# mSD-Shield-Mega_v12.net
KiCad netlist of a schematic drawn in EAGLE
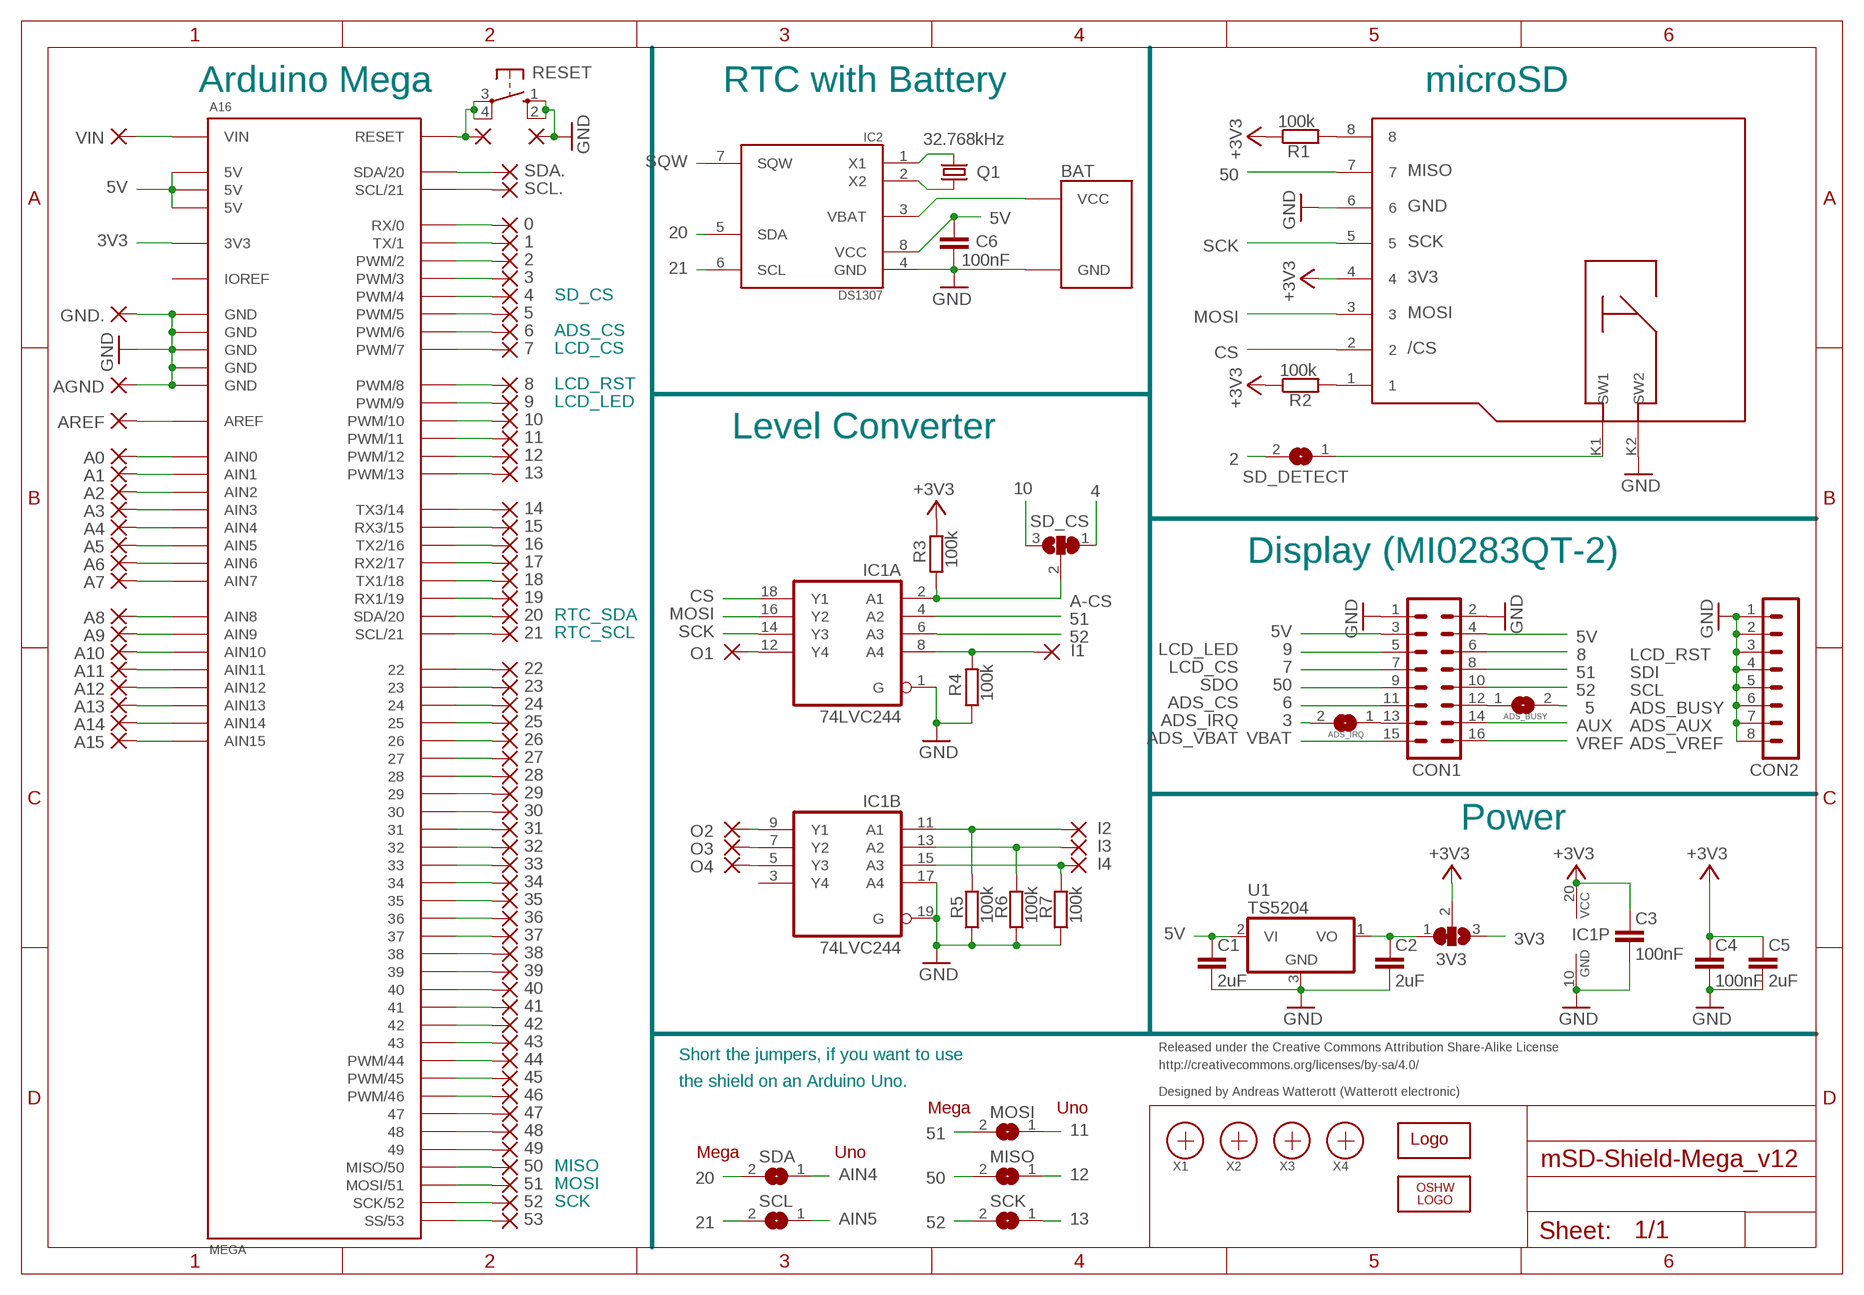
[diagram p0: schematic, sheet 1]

(export (version "E")
  (design (tool "Eeschema 10.0.6"))
  (components
    (comp (ref "0")
      (value "1,6/0,8")
      (footprint "eagle-import:1,6_0,8")
      (libsource (lib "eagle-import") (part "1,6/0,8"))
    )
    (comp (ref "1")
      (value "1,6/0,8")
      (footprint "eagle-import:1,6_0,8")
      (libsource (lib "eagle-import") (part "1,6/0,8"))
    )
    (comp (ref "2")
      (value "1,6/0,8")
      (footprint "eagle-import:1,6_0,8")
      (libsource (lib "eagle-import") (part "1,6/0,8"))
    )
    (comp (ref "3")
      (value "1,6/0,8")
      (footprint "eagle-import:1,6_0,8")
      (libsource (lib "eagle-import") (part "1,6/0,8"))
    )
    (comp (ref "3V3")
      (value "SJ2W")
      (footprint "eagle-import:SJ_2")
      (libsource (lib "eagle-import") (part "SJ2W"))
    )
    (comp (ref "4")
      (value "1,6/0,8")
      (footprint "eagle-import:1,6_0,8")
      (libsource (lib "eagle-import") (part "1,6/0,8"))
    )
    (comp (ref "5")
      (value "1,6/0,8")
      (footprint "eagle-import:1,6_0,8")
      (libsource (lib "eagle-import") (part "1,6/0,8"))
    )
    (comp (ref "6")
      (value "1,6/0,8")
      (footprint "eagle-import:1,6_0,8")
      (libsource (lib "eagle-import") (part "1,6/0,8"))
    )
    (comp (ref "7")
      (value "1,6/0,8")
      (footprint "eagle-import:1,6_0,8")
      (libsource (lib "eagle-import") (part "1,6/0,8"))
    )
    (comp (ref "8")
      (value "1,6/0,8")
      (footprint "eagle-import:1,6_0,8")
      (libsource (lib "eagle-import") (part "1,6/0,8"))
    )
    (comp (ref "9")
      (value "1,6/0,8")
      (footprint "eagle-import:1,6_0,8")
      (libsource (lib "eagle-import") (part "1,6/0,8"))
    )
    (comp (ref "10")
      (value "1,6/0,8")
      (footprint "eagle-import:1,6_0,8")
      (libsource (lib "eagle-import") (part "1,6/0,8"))
    )
    (comp (ref "11")
      (value "1,6/0,8")
      (footprint "eagle-import:1,6_0,8")
      (libsource (lib "eagle-import") (part "1,6/0,8"))
    )
    (comp (ref "12")
      (value "1,6/0,8")
      (footprint "eagle-import:1,6_0,8")
      (libsource (lib "eagle-import") (part "1,6/0,8"))
    )
    (comp (ref "13")
      (value "1,6/0,8")
      (footprint "eagle-import:1,6_0,8")
      (libsource (lib "eagle-import") (part "1,6/0,8"))
    )
    (comp (ref "14")
      (value "1,6/0,8")
      (footprint "eagle-import:1,6_0,8")
      (libsource (lib "eagle-import") (part "1,6/0,8"))
    )
    (comp (ref "15")
      (value "1,6/0,8")
      (footprint "eagle-import:1,6_0,8")
      (libsource (lib "eagle-import") (part "1,6/0,8"))
    )
    (comp (ref "16")
      (value "1,6/0,8")
      (footprint "eagle-import:1,6_0,8")
      (libsource (lib "eagle-import") (part "1,6/0,8"))
    )
    (comp (ref "17")
      (value "1,6/0,8")
      (footprint "eagle-import:1,6_0,8")
      (libsource (lib "eagle-import") (part "1,6/0,8"))
    )
    (comp (ref "18")
      (value "1,6/0,8")
      (footprint "eagle-import:1,6_0,8")
      (libsource (lib "eagle-import") (part "1,6/0,8"))
    )
    (comp (ref "19")
      (value "1,6/0,8")
      (footprint "eagle-import:1,6_0,8")
      (libsource (lib "eagle-import") (part "1,6/0,8"))
    )
    (comp (ref "20")
      (value "1,6/0,8")
      (footprint "eagle-import:1,6_0,8")
      (libsource (lib "eagle-import") (part "1,6/0,8"))
    )
    (comp (ref "21")
      (value "1,6/0,8")
      (footprint "eagle-import:1,6_0,8")
      (libsource (lib "eagle-import") (part "1,6/0,8"))
    )
    (comp (ref "22")
      (value "1,6/0,8")
      (footprint "eagle-import:1,6_0,8")
      (libsource (lib "eagle-import") (part "1,6/0,8"))
    )
    (comp (ref "23")
      (value "1,6/0,8")
      (footprint "eagle-import:1,6_0,8")
      (libsource (lib "eagle-import") (part "1,6/0,8"))
    )
    (comp (ref "24")
      (value "1,6/0,8")
      (footprint "eagle-import:1,6_0,8")
      (libsource (lib "eagle-import") (part "1,6/0,8"))
    )
    (comp (ref "25")
      (value "1,6/0,8")
      (footprint "eagle-import:1,6_0,8")
      (libsource (lib "eagle-import") (part "1,6/0,8"))
    )
    (comp (ref "26")
      (value "1,6/0,8")
      (footprint "eagle-import:1,6_0,8")
      (libsource (lib "eagle-import") (part "1,6/0,8"))
    )
    (comp (ref "27")
      (value "1,6/0,8")
      (footprint "eagle-import:1,6_0,8")
      (libsource (lib "eagle-import") (part "1,6/0,8"))
    )
    (comp (ref "28")
      (value "1,6/0,8")
      (footprint "eagle-import:1,6_0,8")
      (libsource (lib "eagle-import") (part "1,6/0,8"))
    )
    (comp (ref "29")
      (value "1,6/0,8")
      (footprint "eagle-import:1,6_0,8")
      (libsource (lib "eagle-import") (part "1,6/0,8"))
    )
    (comp (ref "30")
      (value "1,6/0,8")
      (footprint "eagle-import:1,6_0,8")
      (libsource (lib "eagle-import") (part "1,6/0,8"))
    )
    (comp (ref "31")
      (value "1,6/0,8")
      (footprint "eagle-import:1,6_0,8")
      (libsource (lib "eagle-import") (part "1,6/0,8"))
    )
    (comp (ref "32")
      (value "1,6/0,8")
      (footprint "eagle-import:1,6_0,8")
      (libsource (lib "eagle-import") (part "1,6/0,8"))
    )
    (comp (ref "33")
      (value "1,6/0,8")
      (footprint "eagle-import:1,6_0,8")
      (libsource (lib "eagle-import") (part "1,6/0,8"))
    )
    (comp (ref "34")
      (value "1,6/0,8")
      (footprint "eagle-import:1,6_0,8")
      (libsource (lib "eagle-import") (part "1,6/0,8"))
    )
    (comp (ref "35")
      (value "1,6/0,8")
      (footprint "eagle-import:1,6_0,8")
      (libsource (lib "eagle-import") (part "1,6/0,8"))
    )
    (comp (ref "36")
      (value "1,6/0,8")
      (footprint "eagle-import:1,6_0,8")
      (libsource (lib "eagle-import") (part "1,6/0,8"))
    )
    (comp (ref "37")
      (value "1,6/0,8")
      (footprint "eagle-import:1,6_0,8")
      (libsource (lib "eagle-import") (part "1,6/0,8"))
    )
    (comp (ref "38")
      (value "1,6/0,8")
      (footprint "eagle-import:1,6_0,8")
      (libsource (lib "eagle-import") (part "1,6/0,8"))
    )
    (comp (ref "39")
      (value "1,6/0,8")
      (footprint "eagle-import:1,6_0,8")
      (libsource (lib "eagle-import") (part "1,6/0,8"))
    )
    (comp (ref "40")
      (value "1,6/0,8")
      (footprint "eagle-import:1,6_0,8")
      (libsource (lib "eagle-import") (part "1,6/0,8"))
    )
    (comp (ref "41")
      (value "1,6/0,8")
      (footprint "eagle-import:1,6_0,8")
      (libsource (lib "eagle-import") (part "1,6/0,8"))
    )
    (comp (ref "42")
      (value "1,6/0,8")
      (footprint "eagle-import:1,6_0,8")
      (libsource (lib "eagle-import") (part "1,6/0,8"))
    )
    (comp (ref "43")
      (value "1,6/0,8")
      (footprint "eagle-import:1,6_0,8")
      (libsource (lib "eagle-import") (part "1,6/0,8"))
    )
    (comp (ref "44")
      (value "1,6/0,8")
      (footprint "eagle-import:1,6_0,8")
      (libsource (lib "eagle-import") (part "1,6/0,8"))
    )
    (comp (ref "45")
      (value "1,6/0,8")
      (footprint "eagle-import:1,6_0,8")
      (libsource (lib "eagle-import") (part "1,6/0,8"))
    )
    (comp (ref "46")
      (value "1,6/0,8")
      (footprint "eagle-import:1,6_0,8")
      (libsource (lib "eagle-import") (part "1,6/0,8"))
    )
    (comp (ref "47")
      (value "1,6/0,8")
      (footprint "eagle-import:1,6_0,8")
      (libsource (lib "eagle-import") (part "1,6/0,8"))
    )
    (comp (ref "48")
      (value "1,6/0,8")
      (footprint "eagle-import:1,6_0,8")
      (libsource (lib "eagle-import") (part "1,6/0,8"))
    )
    (comp (ref "49")
      (value "1,6/0,8")
      (footprint "eagle-import:1,6_0,8")
      (libsource (lib "eagle-import") (part "1,6/0,8"))
    )
    (comp (ref "50")
      (value "1,6/0,8")
      (footprint "eagle-import:1,6_0,8")
      (libsource (lib "eagle-import") (part "1,6/0,8"))
    )
    (comp (ref "51")
      (value "1,6/0,8")
      (footprint "eagle-import:1,6_0,8")
      (libsource (lib "eagle-import") (part "1,6/0,8"))
    )
    (comp (ref "52")
      (value "1,6/0,8")
      (footprint "eagle-import:1,6_0,8")
      (libsource (lib "eagle-import") (part "1,6/0,8"))
    )
    (comp (ref "53")
      (value "1,6/0,8")
      (footprint "eagle-import:1,6_0,8")
      (libsource (lib "eagle-import") (part "1,6/0,8"))
    )
    (comp (ref "A0")
      (value "1,6/0,8")
      (footprint "eagle-import:1,6_0,8")
      (libsource (lib "eagle-import") (part "1,6/0,8"))
    )
    (comp (ref "A1")
      (value "1,6/0,8")
      (footprint "eagle-import:1,6_0,8")
      (libsource (lib "eagle-import") (part "1,6/0,8"))
    )
    (comp (ref "A2")
      (value "1,6/0,8")
      (footprint "eagle-import:1,6_0,8")
      (libsource (lib "eagle-import") (part "1,6/0,8"))
    )
    (comp (ref "A3")
      (value "1,6/0,8")
      (footprint "eagle-import:1,6_0,8")
      (libsource (lib "eagle-import") (part "1,6/0,8"))
    )
    (comp (ref "A4")
      (value "1,6/0,8")
      (footprint "eagle-import:1,6_0,8")
      (libsource (lib "eagle-import") (part "1,6/0,8"))
    )
    (comp (ref "A5")
      (value "1,6/0,8")
      (footprint "eagle-import:1,6_0,8")
      (libsource (lib "eagle-import") (part "1,6/0,8"))
    )
    (comp (ref "A6")
      (value "1,6/0,8")
      (footprint "eagle-import:1,6_0,8")
      (libsource (lib "eagle-import") (part "1,6/0,8"))
    )
    (comp (ref "A7")
      (value "1,6/0,8")
      (footprint "eagle-import:1,6_0,8")
      (libsource (lib "eagle-import") (part "1,6/0,8"))
    )
    (comp (ref "A8")
      (value "1,6/0,8")
      (footprint "eagle-import:1,6_0,8")
      (libsource (lib "eagle-import") (part "1,6/0,8"))
    )
    (comp (ref "A9")
      (value "1,6/0,8")
      (footprint "eagle-import:1,6_0,8")
      (libsource (lib "eagle-import") (part "1,6/0,8"))
    )
    (comp (ref "A10")
      (value "1,6/0,8")
      (footprint "eagle-import:1,6_0,8")
      (libsource (lib "eagle-import") (part "1,6/0,8"))
    )
    (comp (ref "A11")
      (value "1,6/0,8")
      (footprint "eagle-import:1,6_0,8")
      (libsource (lib "eagle-import") (part "1,6/0,8"))
    )
    (comp (ref "A12")
      (value "1,6/0,8")
      (footprint "eagle-import:1,6_0,8")
      (libsource (lib "eagle-import") (part "1,6/0,8"))
    )
    (comp (ref "A13")
      (value "1,6/0,8")
      (footprint "eagle-import:1,6_0,8")
      (libsource (lib "eagle-import") (part "1,6/0,8"))
    )
    (comp (ref "A14")
      (value "1,6/0,8")
      (footprint "eagle-import:1,6_0,8")
      (libsource (lib "eagle-import") (part "1,6/0,8"))
    )
    (comp (ref "A15")
      (value "1,6/0,8")
      (footprint "eagle-import:1,6_0,8")
      (libsource (lib "eagle-import") (part "1,6/0,8"))
    )
    (comp (ref "A16")
      (value "MEGA")
      (footprint "eagle-import:MEGA")
      (libsource (lib "eagle-import") (part "MEGA"))
    )
    (comp (ref "ADS_BUSY")
      (value "SJ")
      (footprint "eagle-import:SJ")
      (libsource (lib "eagle-import") (part "SJ"))
    )
    (comp (ref "ADS_IRQ")
      (value "SJ")
      (footprint "eagle-import:SJ")
      (libsource (lib "eagle-import") (part "SJ"))
    )
    (comp (ref "AGND")
      (value "1,6/0,8")
      (footprint "eagle-import:1,6_0,8")
      (libsource (lib "eagle-import") (part "1,6/0,8"))
    )
    (comp (ref "AREF")
      (value "1,6/0,8")
      (footprint "eagle-import:1,6_0,8")
      (libsource (lib "eagle-import") (part "1,6/0,8"))
    )
    (comp (ref "BAT")
      (value "4UC-05581")
      (footprint "eagle-import:4UC-05581")
      (libsource (lib "eagle-import") (part "4UC-05581"))
    )
    (comp (ref "C1")
      (value "2uF")
      (footprint "eagle-import:C0805")
      (libsource (lib "eagle-import") (part "C-EUC0805"))
    )
    (comp (ref "C2")
      (value "2uF")
      (footprint "eagle-import:C0805")
      (libsource (lib "eagle-import") (part "C-EUC0805"))
    )
    (comp (ref "C3")
      (value "100nF")
      (footprint "eagle-import:C0603")
      (libsource (lib "eagle-import") (part "C-EUC0603"))
    )
    (comp (ref "C4")
      (value "100nF")
      (footprint "eagle-import:C0603")
      (libsource (lib "eagle-import") (part "C-EUC0603"))
    )
    (comp (ref "C5")
      (value "2uF")
      (footprint "eagle-import:C0603")
      (libsource (lib "eagle-import") (part "C-EUC0603"))
    )
    (comp (ref "C6")
      (value "100nF")
      (footprint "eagle-import:C0603")
      (libsource (lib "eagle-import") (part "C-EUC0603"))
    )
    (comp (ref "CON1")
      (value "MA08-2")
      (footprint "eagle-import:MA08-2")
      (libsource (lib "eagle-import") (part "MA08-2"))
    )
    (comp (ref "CON2")
      (value "MA08-1")
      (footprint "eagle-import:MA08-1")
      (libsource (lib "eagle-import") (part "MA08-1"))
    )
    (comp (ref "GND")
      (value "SMD2")
      (footprint "eagle-import:SMD1,27-2,54")
      (libsource (lib "eagle-import") (part "SMD2"))
    )
    (comp (ref "GND.")
      (value "1,6/0,8")
      (footprint "eagle-import:1,6_0,8")
      (libsource (lib "eagle-import") (part "1,6/0,8"))
    )
    (comp (ref "I1")
      (value "SMD2")
      (footprint "eagle-import:SMD1,27-2,54")
      (libsource (lib "eagle-import") (part "SMD2"))
    )
    (comp (ref "I2")
      (value "SMD2")
      (footprint "eagle-import:SMD1,27-2,54")
      (libsource (lib "eagle-import") (part "SMD2"))
    )
    (comp (ref "I3")
      (value "SMD2")
      (footprint "eagle-import:SMD1,27-2,54")
      (libsource (lib "eagle-import") (part "SMD2"))
    )
    (comp (ref "I4")
      (value "SMD2")
      (footprint "eagle-import:SMD1,27-2,54")
      (libsource (lib "eagle-import") (part "SMD2"))
    )
    (comp (ref "IC1")
      (value "74LVC244")
      (footprint "eagle-import:SO20W")
      (libsource (lib "eagle-import") (part "74244DWHC"))
    )
    (comp (ref "IC2")
      (value "DS1307")
      (footprint "eagle-import:SO8")
      (libsource (lib "eagle-import") (part "DS1307"))
    )
    (comp (ref "LOGO1")
      (value "WE-LOGO")
      (footprint "eagle-import:WE-LOGO")
      (libsource (lib "eagle-import") (part "WE-LOGOPLACE"))
    )
    (comp (ref "LOGO2")
      (value "OSHW_LOGO_6MILX0100-NT")
      (footprint "eagle-import:OSHW_6X100_NOTEXT")
      (libsource (lib "eagle-import") (part "OSHW_LOGO_6MILX0100-NT"))
    )
    (comp (ref "MISO")
      (value "SJ")
      (footprint "eagle-import:SJ")
      (libsource (lib "eagle-import") (part "SJ"))
    )
    (comp (ref "MOSI")
      (value "SJ")
      (footprint "eagle-import:SJ")
      (libsource (lib "eagle-import") (part "SJ"))
    )
    (comp (ref "O1")
      (value "SMD2")
      (footprint "eagle-import:SMD1,27-2,54")
      (libsource (lib "eagle-import") (part "SMD2"))
    )
    (comp (ref "O2")
      (value "SMD2")
      (footprint "eagle-import:SMD1,27-2,54")
      (libsource (lib "eagle-import") (part "SMD2"))
    )
    (comp (ref "O3")
      (value "SMD2")
      (footprint "eagle-import:SMD1,27-2,54")
      (libsource (lib "eagle-import") (part "SMD2"))
    )
    (comp (ref "O4")
      (value "SMD2")
      (footprint "eagle-import:SMD1,27-2,54")
      (libsource (lib "eagle-import") (part "SMD2"))
    )
    (comp (ref "Q1")
      (value "32.768kHz")
      (footprint "eagle-import:TC26V")
      (libsource (lib "eagle-import") (part "CRYSTALTC26V"))
    )
    (comp (ref "R1")
      (value "100k")
      (footprint "eagle-import:R0603")
      (libsource (lib "eagle-import") (part "R-EU_R0603"))
    )
    (comp (ref "R2")
      (value "100k")
      (footprint "eagle-import:R0603")
      (libsource (lib "eagle-import") (part "R-EU_R0603"))
    )
    (comp (ref "R3")
      (value "100k")
      (footprint "eagle-import:R0603")
      (libsource (lib "eagle-import") (part "R-EU_R0603"))
    )
    (comp (ref "R4")
      (value "100k")
      (footprint "eagle-import:R0603")
      (libsource (lib "eagle-import") (part "R-EU_R0603"))
    )
    (comp (ref "R5")
      (value "100k")
      (footprint "eagle-import:R0603")
      (libsource (lib "eagle-import") (part "R-EU_R0603"))
    )
    (comp (ref "R6")
      (value "100k")
      (footprint "eagle-import:R0603")
      (libsource (lib "eagle-import") (part "R-EU_R0603"))
    )
    (comp (ref "R7")
      (value "100k")
      (footprint "eagle-import:R0603")
      (libsource (lib "eagle-import") (part "R-EU_R0603"))
    )
    (comp (ref "RESET")
      (value "10-XX")
      (footprint "eagle-import:B3F-10XX")
      (fields (field (name "MPN") "B3F-1000"))
      (libsource (lib "eagle-import") (part "10-XX"))
    )
    (comp (ref "RST")
      (value "SMD2")
      (footprint "eagle-import:SMD1,27-2,54")
      (libsource (lib "eagle-import") (part "SMD2"))
    )
    (comp (ref "SCK") (value "SJ") (footprint "eagle-import:SJ") (libsource (lib "eagle-import") (part "SJ")))
    (comp (ref "SCL") (value "SJ") (footprint "eagle-import:SJ") (libsource (lib "eagle-import") (part "SJ")))
    (comp (ref "SCL.")
      (value "1,6/0,8")
      (footprint "eagle-import:1,6_0,8")
      (libsource (lib "eagle-import") (part "1,6/0,8"))
    )
    (comp (ref "SDA") (value "SJ") (footprint "eagle-import:SJ") (libsource (lib "eagle-import") (part "SJ")))
    (comp (ref "SDA.")
      (value "1,6/0,8")
      (footprint "eagle-import:1,6_0,8")
      (libsource (lib "eagle-import") (part "1,6/0,8"))
    )
    (comp (ref "SD_CS")
      (value "SJ2W")
      (footprint "eagle-import:SJ_2")
      (libsource (lib "eagle-import") (part "SJ2W"))
    )
    (comp (ref "SD_DETECT")
      (value "SJ")
      (footprint "eagle-import:SJ")
      (libsource (lib "eagle-import") (part "SJ"))
    )
    (comp (ref "U1")
      (value "TS5204")
      (footprint "eagle-import:SOT23")
      (libsource (lib "eagle-import") (part "TS5204"))
    )
    (comp (ref "VIN")
      (value "1,6/0,8")
      (footprint "eagle-import:1,6_0,8")
      (libsource (lib "eagle-import") (part "1,6/0,8"))
    )
    (comp (ref "X1")
      (value "PASSER")
      (footprint "eagle-import:PASSER")
      (libsource (lib "eagle-import") (part "PASSER"))
    )
    (comp (ref "X2")
      (value "PASSER")
      (footprint "eagle-import:PASSER")
      (libsource (lib "eagle-import") (part "PASSER"))
    )
    (comp (ref "X3")
      (value "PASSER")
      (footprint "eagle-import:PASSER")
      (libsource (lib "eagle-import") (part "PASSER"))
    )
    (comp (ref "X4")
      (value "PASSER")
      (footprint "eagle-import:PASSER")
      (libsource (lib "eagle-import") (part "PASSER"))
    )
    (comp (ref "X5")
      (value "MICRO-SD")
      (footprint "eagle-import:MICRO-SD")
      (libsource (lib "eagle-import") (part "MICRO-SD"))
    )
  )
  (nets
    (net (code "1") (name "+3V3") (class "Default")
      (node (ref "3V3") (pin "2") (pinfunction "2_2") (pintype "passive"))
      (node (ref "C3") (pin "1") (pinfunction "1_1") (pintype "passive"))
      (node (ref "C4") (pin "1") (pinfunction "1_1") (pintype "passive"))
      (node (ref "C5") (pin "1") (pinfunction "1_1") (pintype "passive"))
      (node (ref "IC1") (pin "20") (pinfunction "VCC_20") (pintype "power_in"))
      (node (ref "R1") (pin "1") (pinfunction "1_1") (pintype "passive"))
      (node (ref "R2") (pin "1") (pinfunction "1_1") (pintype "passive"))
      (node (ref "R3") (pin "2") (pinfunction "2_2") (pintype "passive"))
      (node (ref "X5") (pin "4") (pinfunction "4_4") (pintype "bidirectional"))
    )
    (net (code "2") (name "/2") (class "Default")
      (node (ref "2") (pin "1") (pinfunction "P_1") (pintype "passive"))
      (node (ref "A16") (pin "2") (pinfunction "PWM/2_2") (pintype "bidirectional"))
      (node (ref "SD_DETECT") (pin "2") (pinfunction "2_2") (pintype "passive"))
    )
    (net (code "3") (name "/3") (class "Default")
      (node (ref "3") (pin "1") (pinfunction "P_1") (pintype "passive"))
      (node (ref "A16") (pin "3") (pinfunction "PWM/3_3") (pintype "bidirectional"))
      (node (ref "ADS_IRQ") (pin "2") (pinfunction "2_2") (pintype "passive"))
    )
    (net (code "4") (name "/3V3") (class "Default")
      (node (ref "3V3") (pin "3") (pinfunction "3_3") (pintype "passive"))
      (node (ref "A16") (pin "3V3") (pinfunction "3V3_3V3") (pintype "power_in"))
    )
    (net (code "5") (name "/4") (class "Default")
      (node (ref "4") (pin "1") (pinfunction "P_1") (pintype "passive"))
      (node (ref "A16") (pin "4") (pinfunction "PWM/4_4") (pintype "bidirectional"))
      (node (ref "SD_CS") (pin "1") (pinfunction "1_1") (pintype "passive"))
    )
    (net (code "6") (name "/5") (class "Default")
      (node (ref "5") (pin "1") (pinfunction "P_1") (pintype "passive"))
      (node (ref "A16") (pin "5") (pinfunction "PWM/5_5") (pintype "bidirectional"))
      (node (ref "ADS_BUSY") (pin "2") (pinfunction "2_2") (pintype "passive"))
    )
    (net (code "7") (name "/5V") (class "Default")
      (node (ref "A16") (pin "5V1") (pinfunction "5V_5V1") (pintype "power_in"))
      (node (ref "A16") (pin "5V2") (pinfunction "5V_5V2") (pintype "power_in"))
      (node (ref "A16") (pin "5V3") (pinfunction "5V_5V3") (pintype "power_in"))
      (node (ref "C1") (pin "1") (pinfunction "1_1") (pintype "passive"))
      (node (ref "C6") (pin "2") (pinfunction "2_2") (pintype "passive"))
      (node (ref "CON1") (pin "3") (pinfunction "3_3") (pintype "passive"))
      (node (ref "CON1") (pin "4") (pinfunction "4_4") (pintype "passive"))
      (node (ref "IC2") (pin "8") (pinfunction "VCC_8") (pintype "power_in"))
      (node (ref "U1") (pin "2") (pinfunction "VI_2") (pintype "input"))
    )
    (net (code "8") (name "/6") (class "Default")
      (node (ref "6") (pin "1") (pinfunction "P_1") (pintype "passive"))
      (node (ref "A16") (pin "6") (pinfunction "PWM/6_6") (pintype "bidirectional"))
      (node (ref "CON1") (pin "11") (pinfunction "11_11") (pintype "passive"))
    )
    (net (code "9") (name "/7") (class "Default")
      (node (ref "7") (pin "1") (pinfunction "P_1") (pintype "passive"))
      (node (ref "A16") (pin "7") (pinfunction "PWM/7_7") (pintype "bidirectional"))
      (node (ref "CON1") (pin "7") (pinfunction "7_7") (pintype "passive"))
    )
    (net (code "10") (name "/8") (class "Default")
      (node (ref "8") (pin "1") (pinfunction "P_1") (pintype "passive"))
      (node (ref "A16") (pin "8") (pinfunction "PWM/8_8") (pintype "bidirectional"))
      (node (ref "CON1") (pin "6") (pinfunction "6_6") (pintype "passive"))
    )
    (net (code "11") (name "/9") (class "Default")
      (node (ref "9") (pin "1") (pinfunction "P_1") (pintype "passive"))
      (node (ref "A16") (pin "9") (pinfunction "PWM/9_9") (pintype "bidirectional"))
      (node (ref "CON1") (pin "5") (pinfunction "5_5") (pintype "passive"))
    )
    (net (code "12") (name "/10") (class "Default")
      (node (ref "10") (pin "1") (pinfunction "P_1") (pintype "passive"))
      (node (ref "A16") (pin "10") (pinfunction "PWM/10_10") (pintype "bidirectional"))
      (node (ref "SD_CS") (pin "3") (pinfunction "3_3") (pintype "passive"))
    )
    (net (code "13") (name "/11") (class "Default")
      (node (ref "11") (pin "1") (pinfunction "P_1") (pintype "passive"))
      (node (ref "A16") (pin "11") (pinfunction "PWM/11_11") (pintype "bidirectional"))
      (node (ref "MOSI") (pin "1") (pinfunction "1_1") (pintype "passive"))
    )
    (net (code "14") (name "/12") (class "Default")
      (node (ref "12") (pin "1") (pinfunction "P_1") (pintype "passive"))
      (node (ref "A16") (pin "12") (pinfunction "PWM/12_12") (pintype "bidirectional"))
      (node (ref "MISO") (pin "1") (pinfunction "1_1") (pintype "passive"))
    )
    (net (code "15") (name "/13") (class "Default")
      (node (ref "13") (pin "1") (pinfunction "P_1") (pintype "passive"))
      (node (ref "A16") (pin "13") (pinfunction "PWM/13_13") (pintype "bidirectional"))
      (node (ref "SCK") (pin "1") (pinfunction "1_1") (pintype "passive"))
    )
    (net (code "16") (name "/20") (class "Default")
      (node (ref "20") (pin "1") (pinfunction "P_1") (pintype "passive"))
      (node (ref "A16") (pin "20") (pinfunction "SDA/20_20") (pintype "bidirectional"))
      (node (ref "IC2") (pin "5") (pinfunction "SDA_5") (pintype "bidirectional"))
      (node (ref "SDA") (pin "2") (pinfunction "2_2") (pintype "passive"))
    )
    (net (code "17") (name "/21") (class "Default")
      (node (ref "21") (pin "1") (pinfunction "P_1") (pintype "passive"))
      (node (ref "A16") (pin "21") (pinfunction "SCL/21_21") (pintype "bidirectional"))
      (node (ref "IC2") (pin "6") (pinfunction "SCL_6") (pintype "bidirectional"))
      (node (ref "SCL") (pin "2") (pinfunction "2_2") (pintype "passive"))
    )
    (net (code "18") (name "/50") (class "Default")
      (node (ref "50") (pin "1") (pinfunction "P_1") (pintype "passive"))
      (node (ref "A16") (pin "50") (pinfunction "MISO/50_50") (pintype "bidirectional"))
      (node (ref "CON1") (pin "9") (pinfunction "9_9") (pintype "passive"))
      (node (ref "MISO") (pin "2") (pinfunction "2_2") (pintype "passive"))
      (node (ref "X5") (pin "7") (pinfunction "7_7") (pintype "bidirectional"))
    )
    (net (code "19") (name "/51") (class "Default")
      (node (ref "51") (pin "1") (pinfunction "P_1") (pintype "passive"))
      (node (ref "A16") (pin "51") (pinfunction "MOSI/51_51") (pintype "bidirectional"))
      (node (ref "CON1") (pin "8") (pinfunction "8_8") (pintype "passive"))
      (node (ref "IC1") (pin "4") (pinfunction "A2_4") (pintype "input"))
      (node (ref "MOSI") (pin "2") (pinfunction "2_2") (pintype "passive"))
    )
    (net (code "20") (name "/52") (class "Default")
      (node (ref "52") (pin "1") (pinfunction "P_1") (pintype "passive"))
      (node (ref "A16") (pin "52") (pinfunction "SCK/52_52") (pintype "bidirectional"))
      (node (ref "CON1") (pin "10") (pinfunction "10_10") (pintype "passive"))
      (node (ref "IC1") (pin "6") (pinfunction "A3_6") (pintype "input"))
      (node (ref "SCK") (pin "2") (pinfunction "2_2") (pintype "passive"))
    )
    (net (code "21") (name "/A-CS") (class "Default")
      (node (ref "IC1") (pin "2") (pinfunction "A1_2") (pintype "input"))
      (node (ref "R3") (pin "1") (pinfunction "1_1") (pintype "passive"))
      (node (ref "SD_CS") (pin "2") (pinfunction "2_2") (pintype "passive"))
    )
    (net (code "22") (name "/AIN4") (class "Default")
      (node (ref "A16") (pin "AIN4") (pinfunction "AIN4_AIN4") (pintype "bidirectional"))
      (node (ref "A4") (pin "1") (pinfunction "P_1") (pintype "passive"))
      (node (ref "SDA") (pin "1") (pinfunction "1_1") (pintype "passive"))
    )
    (net (code "23") (name "/AIN5") (class "Default")
      (node (ref "A16") (pin "AIN5") (pinfunction "AIN5_AIN5") (pintype "bidirectional"))
      (node (ref "A5") (pin "1") (pinfunction "P_1") (pintype "passive"))
      (node (ref "SCL") (pin "1") (pinfunction "1_1") (pintype "passive"))
    )
    (net (code "24") (name "/AUX") (class "Default")
      (node (ref "CON1") (pin "14") (pinfunction "14_14") (pintype "passive"))
    )
    (net (code "25") (name "/CS") (class "Default")
      (node (ref "IC1") (pin "18") (pinfunction "Y1_18") (pintype "tri_state"))
      (node (ref "X5") (pin "2") (pinfunction "2_2") (pintype "bidirectional"))
    )
    (net (code "26") (name "/IOREF") (class "Default")
      (node (ref "A16") (pin "IOREF") (pinfunction "IOREF_IOREF") (pintype "power_in"))
    )
    (net (code "27") (name "/MOSI") (class "Default")
      (node (ref "IC1") (pin "16") (pinfunction "Y2_16") (pintype "tri_state"))
      (node (ref "X5") (pin "3") (pinfunction "3_3") (pintype "bidirectional"))
    )
    (net (code "28") (name "/SCK") (class "Default")
      (node (ref "IC1") (pin "14") (pinfunction "Y3_14") (pintype "tri_state"))
      (node (ref "X5") (pin "5") (pinfunction "5_5") (pintype "bidirectional"))
    )
    (net (code "29") (name "/SQW") (class "Default")
      (node (ref "IC2") (pin "7") (pinfunction "SQW_7") (pintype "bidirectional"))
    )
    (net (code "30") (name "/VBAT") (class "Default")
      (node (ref "CON1") (pin "15") (pinfunction "15_15") (pintype "passive"))
    )
    (net (code "31") (name "/VREF") (class "Default")
      (node (ref "CON1") (pin "16") (pinfunction "16_16") (pintype "passive"))
    )
    (net (code "32") (name "GND") (class "Default")
      (node (ref "A16") (pin "GND1") (pinfunction "GND_GND1") (pintype "power_in"))
      (node (ref "A16") (pin "GND2") (pinfunction "GND_GND2") (pintype "power_in"))
      (node (ref "A16") (pin "GND3") (pinfunction "GND_GND3") (pintype "power_in"))
      (node (ref "A16") (pin "GND4") (pinfunction "GND_GND4") (pintype "power_in"))
      (node (ref "A16") (pin "GND5") (pinfunction "GND_GND5") (pintype "power_in"))
      (node (ref "AGND") (pin "1") (pinfunction "P_1") (pintype "passive"))
      (node (ref "BAT") (pin "GND") (pinfunction "GND_GND") (pintype "power_in"))
      (node (ref "C1") (pin "2") (pinfunction "2_2") (pintype "passive"))
      (node (ref "C2") (pin "2") (pinfunction "2_2") (pintype "passive"))
      (node (ref "C3") (pin "2") (pinfunction "2_2") (pintype "passive"))
      (node (ref "C4") (pin "2") (pinfunction "2_2") (pintype "passive"))
      (node (ref "C5") (pin "2") (pinfunction "2_2") (pintype "passive"))
      (node (ref "C6") (pin "1") (pinfunction "1_1") (pintype "passive"))
      (node (ref "CON1") (pin "1") (pinfunction "1_1") (pintype "passive"))
      (node (ref "CON1") (pin "2") (pinfunction "2_2") (pintype "passive"))
      (node (ref "CON2") (pin "1") (pinfunction "1_1") (pintype "passive"))
      (node (ref "CON2") (pin "2") (pinfunction "2_2") (pintype "passive"))
      (node (ref "CON2") (pin "3") (pinfunction "3_3") (pintype "passive"))
      (node (ref "CON2") (pin "4") (pinfunction "4_4") (pintype "passive"))
      (node (ref "CON2") (pin "5") (pinfunction "5_5") (pintype "passive"))
      (node (ref "CON2") (pin "6") (pinfunction "6_6") (pintype "passive"))
      (node (ref "CON2") (pin "7") (pinfunction "7_7") (pintype "passive"))
      (node (ref "CON2") (pin "8") (pinfunction "8_8") (pintype "passive"))
      (node (ref "GND") (pin "1") (pinfunction "P_1") (pintype "passive"))
      (node (ref "GND.") (pin "1") (pinfunction "P_1") (pintype "passive"))
      (node (ref "IC1") (pin "1") (pinfunction "G_1") (pintype "input"))
      (node (ref "IC1") (pin "10") (pinfunction "GND_10") (pintype "power_in"))
      (node (ref "IC1") (pin "17") (pinfunction "A4_17") (pintype "input"))
      (node (ref "IC1") (pin "19") (pinfunction "G_19") (pintype "input"))
      (node (ref "IC2") (pin "4") (pinfunction "GND_4") (pintype "power_in"))
      (node (ref "R4") (pin "1") (pinfunction "1_1") (pintype "passive"))
      (node (ref "R5") (pin "1") (pinfunction "1_1") (pintype "passive"))
      (node (ref "R6") (pin "1") (pinfunction "1_1") (pintype "passive"))
      (node (ref "R7") (pin "1") (pinfunction "1_1") (pintype "passive"))
      (node (ref "RESET") (pin "1") (pinfunction "S_1") (pintype "passive"))
      (node (ref "RESET") (pin "2") (pinfunction "S1_2") (pintype "passive"))
      (node (ref "U1") (pin "3") (pinfunction "GND_3") (pintype "passive"))
      (node (ref "X5") (pin "6") (pinfunction "6_6") (pintype "bidirectional"))
      (node (ref "X5") (pin "K2") (pinfunction "SW2_K2") (pintype "bidirectional"))
    )
    (net (code "33") (name "Net-(0-P)") (class "Default")
      (node (ref "0") (pin "1") (pinfunction "P_1") (pintype "passive"))
      (node (ref "A16") (pin "0") (pinfunction "RX/0_0") (pintype "bidirectional"))
    )
    (net (code "34") (name "Net-(1-P)") (class "Default")
      (node (ref "1") (pin "1") (pinfunction "P_1") (pintype "passive"))
      (node (ref "A16") (pin "1") (pinfunction "TX/1_1") (pintype "bidirectional"))
    )
    (net (code "35") (name "Net-(14-P)") (class "Default")
      (node (ref "14") (pin "1") (pinfunction "P_1") (pintype "passive"))
      (node (ref "A16") (pin "14") (pinfunction "TX3/14_14") (pintype "bidirectional"))
    )
    (net (code "36") (name "Net-(15-P)") (class "Default")
      (node (ref "15") (pin "1") (pinfunction "P_1") (pintype "passive"))
      (node (ref "A16") (pin "15") (pinfunction "RX3/15_15") (pintype "bidirectional"))
    )
    (net (code "37") (name "Net-(16-P)") (class "Default")
      (node (ref "16") (pin "1") (pinfunction "P_1") (pintype "passive"))
      (node (ref "A16") (pin "16") (pinfunction "TX2/16_16") (pintype "bidirectional"))
    )
    (net (code "38") (name "Net-(17-P)") (class "Default")
      (node (ref "17") (pin "1") (pinfunction "P_1") (pintype "passive"))
      (node (ref "A16") (pin "17") (pinfunction "RX2/17_17") (pintype "bidirectional"))
    )
    (net (code "39") (name "Net-(18-P)") (class "Default")
      (node (ref "18") (pin "1") (pinfunction "P_1") (pintype "passive"))
      (node (ref "A16") (pin "18") (pinfunction "TX1/18_18") (pintype "bidirectional"))
    )
    (net (code "40") (name "Net-(19-P)") (class "Default")
      (node (ref "19") (pin "1") (pinfunction "P_1") (pintype "passive"))
      (node (ref "A16") (pin "19") (pinfunction "RX1/19_19") (pintype "bidirectional"))
    )
    (net (code "41") (name "Net-(22-P)") (class "Default")
      (node (ref "22") (pin "1") (pinfunction "P_1") (pintype "passive"))
      (node (ref "A16") (pin "22") (pinfunction "22_22") (pintype "bidirectional"))
    )
    (net (code "42") (name "Net-(23-P)") (class "Default")
      (node (ref "23") (pin "1") (pinfunction "P_1") (pintype "passive"))
      (node (ref "A16") (pin "23") (pinfunction "23_23") (pintype "bidirectional"))
    )
    (net (code "43") (name "Net-(24-P)") (class "Default")
      (node (ref "24") (pin "1") (pinfunction "P_1") (pintype "passive"))
      (node (ref "A16") (pin "24") (pinfunction "24_24") (pintype "bidirectional"))
    )
    (net (code "44") (name "Net-(25-P)") (class "Default")
      (node (ref "25") (pin "1") (pinfunction "P_1") (pintype "passive"))
      (node (ref "A16") (pin "25") (pinfunction "25_25") (pintype "bidirectional"))
    )
    (net (code "45") (name "Net-(26-P)") (class "Default")
      (node (ref "26") (pin "1") (pinfunction "P_1") (pintype "passive"))
      (node (ref "A16") (pin "26") (pinfunction "26_26") (pintype "bidirectional"))
    )
    (net (code "46") (name "Net-(27-P)") (class "Default")
      (node (ref "27") (pin "1") (pinfunction "P_1") (pintype "passive"))
      (node (ref "A16") (pin "27") (pinfunction "27_27") (pintype "bidirectional"))
    )
    (net (code "47") (name "Net-(28-P)") (class "Default")
      (node (ref "28") (pin "1") (pinfunction "P_1") (pintype "passive"))
      (node (ref "A16") (pin "28") (pinfunction "28_28") (pintype "bidirectional"))
    )
    (net (code "48") (name "Net-(29-P)") (class "Default")
      (node (ref "29") (pin "1") (pinfunction "P_1") (pintype "passive"))
      (node (ref "A16") (pin "29") (pinfunction "29_29") (pintype "bidirectional"))
    )
    (net (code "49") (name "Net-(30-P)") (class "Default")
      (node (ref "30") (pin "1") (pinfunction "P_1") (pintype "passive"))
      (node (ref "A16") (pin "30") (pinfunction "30_30") (pintype "bidirectional"))
    )
    (net (code "50") (name "Net-(31-P)") (class "Default")
      (node (ref "31") (pin "1") (pinfunction "P_1") (pintype "passive"))
      (node (ref "A16") (pin "31") (pinfunction "31_31") (pintype "bidirectional"))
    )
    (net (code "51") (name "Net-(32-P)") (class "Default")
      (node (ref "32") (pin "1") (pinfunction "P_1") (pintype "passive"))
      (node (ref "A16") (pin "32") (pinfunction "32_32") (pintype "bidirectional"))
    )
    (net (code "52") (name "Net-(33-P)") (class "Default")
      (node (ref "33") (pin "1") (pinfunction "P_1") (pintype "passive"))
      (node (ref "A16") (pin "33") (pinfunction "33_33") (pintype "bidirectional"))
    )
    (net (code "53") (name "Net-(34-P)") (class "Default")
      (node (ref "34") (pin "1") (pinfunction "P_1") (pintype "passive"))
      (node (ref "A16") (pin "34") (pinfunction "34_34") (pintype "bidirectional"))
    )
    (net (code "54") (name "Net-(35-P)") (class "Default")
      (node (ref "35") (pin "1") (pinfunction "P_1") (pintype "passive"))
      (node (ref "A16") (pin "35") (pinfunction "35_35") (pintype "bidirectional"))
    )
    (net (code "55") (name "Net-(36-P)") (class "Default")
      (node (ref "36") (pin "1") (pinfunction "P_1") (pintype "passive"))
      (node (ref "A16") (pin "36") (pinfunction "36_36") (pintype "bidirectional"))
    )
    (net (code "56") (name "Net-(37-P)") (class "Default")
      (node (ref "37") (pin "1") (pinfunction "P_1") (pintype "passive"))
      (node (ref "A16") (pin "37") (pinfunction "37_37") (pintype "bidirectional"))
    )
    (net (code "57") (name "Net-(38-P)") (class "Default")
      (node (ref "38") (pin "1") (pinfunction "P_1") (pintype "passive"))
      (node (ref "A16") (pin "38") (pinfunction "38_38") (pintype "bidirectional"))
    )
    (net (code "58") (name "Net-(39-P)") (class "Default")
      (node (ref "39") (pin "1") (pinfunction "P_1") (pintype "passive"))
      (node (ref "A16") (pin "39") (pinfunction "39_39") (pintype "bidirectional"))
    )
    (net (code "59") (name "Net-(40-P)") (class "Default")
      (node (ref "40") (pin "1") (pinfunction "P_1") (pintype "passive"))
      (node (ref "A16") (pin "40") (pinfunction "40_40") (pintype "bidirectional"))
    )
    (net (code "60") (name "Net-(41-P)") (class "Default")
      (node (ref "41") (pin "1") (pinfunction "P_1") (pintype "passive"))
      (node (ref "A16") (pin "41") (pinfunction "41_41") (pintype "bidirectional"))
    )
    (net (code "61") (name "Net-(42-P)") (class "Default")
      (node (ref "42") (pin "1") (pinfunction "P_1") (pintype "passive"))
      (node (ref "A16") (pin "42") (pinfunction "42_42") (pintype "bidirectional"))
    )
    (net (code "62") (name "Net-(43-P)") (class "Default")
      (node (ref "43") (pin "1") (pinfunction "P_1") (pintype "passive"))
      (node (ref "A16") (pin "43") (pinfunction "43_43") (pintype "bidirectional"))
    )
    (net (code "63") (name "Net-(44-P)") (class "Default")
      (node (ref "44") (pin "1") (pinfunction "P_1") (pintype "passive"))
      (node (ref "A16") (pin "44") (pinfunction "PWM/44_44") (pintype "bidirectional"))
    )
    (net (code "64") (name "Net-(45-P)") (class "Default")
      (node (ref "45") (pin "1") (pinfunction "P_1") (pintype "passive"))
      (node (ref "A16") (pin "45") (pinfunction "PWM/45_45") (pintype "bidirectional"))
    )
    (net (code "65") (name "Net-(46-P)") (class "Default")
      (node (ref "46") (pin "1") (pinfunction "P_1") (pintype "passive"))
      (node (ref "A16") (pin "46") (pinfunction "PWM/46_46") (pintype "bidirectional"))
    )
    (net (code "66") (name "Net-(47-P)") (class "Default")
      (node (ref "47") (pin "1") (pinfunction "P_1") (pintype "passive"))
      (node (ref "A16") (pin "47") (pinfunction "47_47") (pintype "bidirectional"))
    )
    (net (code "67") (name "Net-(48-P)") (class "Default")
      (node (ref "48") (pin "1") (pinfunction "P_1") (pintype "passive"))
      (node (ref "A16") (pin "48") (pinfunction "48_48") (pintype "bidirectional"))
    )
    (net (code "68") (name "Net-(49-P)") (class "Default")
      (node (ref "49") (pin "1") (pinfunction "P_1") (pintype "passive"))
      (node (ref "A16") (pin "49") (pinfunction "49_49") (pintype "bidirectional"))
    )
    (net (code "69") (name "Net-(53-P)") (class "Default")
      (node (ref "53") (pin "1") (pinfunction "P_1") (pintype "passive"))
      (node (ref "A16") (pin "53") (pinfunction "SS/53_53") (pintype "bidirectional"))
    )
    (net (code "70") (name "Net-(A0-P)") (class "Default")
      (node (ref "A0") (pin "1") (pinfunction "P_1") (pintype "passive"))
      (node (ref "A16") (pin "AIN0") (pinfunction "AIN0_AIN0") (pintype "bidirectional"))
    )
    (net (code "71") (name "Net-(A1-P)") (class "Default")
      (node (ref "A1") (pin "1") (pinfunction "P_1") (pintype "passive"))
      (node (ref "A16") (pin "AIN1") (pinfunction "AIN1_AIN1") (pintype "bidirectional"))
    )
    (net (code "72") (name "Net-(A2-P)") (class "Default")
      (node (ref "A16") (pin "AIN2") (pinfunction "AIN2_AIN2") (pintype "bidirectional"))
      (node (ref "A2") (pin "1") (pinfunction "P_1") (pintype "passive"))
    )
    (net (code "73") (name "Net-(A3-P)") (class "Default")
      (node (ref "A16") (pin "AIN3") (pinfunction "AIN3_AIN3") (pintype "bidirectional"))
      (node (ref "A3") (pin "1") (pinfunction "P_1") (pintype "passive"))
    )
    (net (code "74") (name "Net-(A6-P)") (class "Default")
      (node (ref "A16") (pin "AIN6") (pinfunction "AIN6_AIN6") (pintype "bidirectional"))
      (node (ref "A6") (pin "1") (pinfunction "P_1") (pintype "passive"))
    )
    (net (code "75") (name "Net-(A7-P)") (class "Default")
      (node (ref "A16") (pin "AIN7") (pinfunction "AIN7_AIN7") (pintype "bidirectional"))
      (node (ref "A7") (pin "1") (pinfunction "P_1") (pintype "passive"))
    )
    (net (code "76") (name "Net-(A8-P)") (class "Default")
      (node (ref "A16") (pin "AIN8") (pinfunction "AIN8_AIN8") (pintype "bidirectional"))
      (node (ref "A8") (pin "1") (pinfunction "P_1") (pintype "passive"))
    )
    (net (code "77") (name "Net-(A9-P)") (class "Default")
      (node (ref "A16") (pin "AIN9") (pinfunction "AIN9_AIN9") (pintype "bidirectional"))
      (node (ref "A9") (pin "1") (pinfunction "P_1") (pintype "passive"))
    )
    (net (code "78") (name "Net-(A10-P)") (class "Default")
      (node (ref "A10") (pin "1") (pinfunction "P_1") (pintype "passive"))
      (node (ref "A16") (pin "AIN10") (pinfunction "AIN10_AIN10") (pintype "bidirectional"))
    )
    (net (code "79") (name "Net-(A11-P)") (class "Default")
      (node (ref "A11") (pin "1") (pinfunction "P_1") (pintype "passive"))
      (node (ref "A16") (pin "AIN11") (pinfunction "AIN11_AIN11") (pintype "bidirectional"))
    )
    (net (code "80") (name "Net-(A12-P)") (class "Default")
      (node (ref "A12") (pin "1") (pinfunction "P_1") (pintype "passive"))
      (node (ref "A16") (pin "AIN12") (pinfunction "AIN12_AIN12") (pintype "bidirectional"))
    )
    (net (code "81") (name "Net-(A13-P)") (class "Default")
      (node (ref "A13") (pin "1") (pinfunction "P_1") (pintype "passive"))
      (node (ref "A16") (pin "AIN13") (pinfunction "AIN13_AIN13") (pintype "bidirectional"))
    )
    (net (code "82") (name "Net-(A14-P)") (class "Default")
      (node (ref "A14") (pin "1") (pinfunction "P_1") (pintype "passive"))
      (node (ref "A16") (pin "AIN14") (pinfunction "AIN14_AIN14") (pintype "bidirectional"))
    )
    (net (code "83") (name "Net-(A15-P)") (class "Default")
      (node (ref "A15") (pin "1") (pinfunction "P_1") (pintype "passive"))
      (node (ref "A16") (pin "AIN15") (pinfunction "AIN15_AIN15") (pintype "bidirectional"))
    )
    (net (code "84") (name "Net-(A16-RESET)") (class "Default")
      (node (ref "A16") (pin "RST") (pinfunction "RESET_RST") (pintype "bidirectional"))
      (node (ref "RESET") (pin "3") (pinfunction "P_3") (pintype "passive"))
      (node (ref "RESET") (pin "4") (pinfunction "P1_4") (pintype "passive"))
      (node (ref "RST") (pin "1") (pinfunction "P_1") (pintype "passive"))
    )
    (net (code "85") (name "Net-(ADS_BUSY-Pad1)") (class "Default")
      (node (ref "ADS_BUSY") (pin "1") (pinfunction "1_1") (pintype "passive"))
      (node (ref "CON1") (pin "12") (pinfunction "12_12") (pintype "passive"))
    )
    (net (code "86") (name "Net-(ADS_IRQ-Pad1)") (class "Default")
      (node (ref "ADS_IRQ") (pin "1") (pinfunction "1_1") (pintype "passive"))
      (node (ref "CON1") (pin "13") (pinfunction "13_13") (pintype "passive"))
    )
    (net (code "87") (name "Net-(AREF-P)") (class "Default")
      (node (ref "A16") (pin "AREF") (pinfunction "AREF_AREF") (pintype "power_in"))
      (node (ref "AREF") (pin "1") (pinfunction "P_1") (pintype "passive"))
    )
    (net (code "88") (name "Net-(I1-P)") (class "Default")
      (node (ref "I1") (pin "1") (pinfunction "P_1") (pintype "passive"))
      (node (ref "IC1") (pin "8") (pinfunction "A4_8") (pintype "input"))
      (node (ref "R4") (pin "2") (pinfunction "2_2") (pintype "passive"))
    )
    (net (code "89") (name "Net-(I2-P)") (class "Default")
      (node (ref "I2") (pin "1") (pinfunction "P_1") (pintype "passive"))
      (node (ref "IC1") (pin "11") (pinfunction "A1_11") (pintype "input"))
      (node (ref "R5") (pin "2") (pinfunction "2_2") (pintype "passive"))
    )
    (net (code "90") (name "Net-(I3-P)") (class "Default")
      (node (ref "I3") (pin "1") (pinfunction "P_1") (pintype "passive"))
      (node (ref "IC1") (pin "13") (pinfunction "A2_13") (pintype "input"))
      (node (ref "R6") (pin "2") (pinfunction "2_2") (pintype "passive"))
    )
    (net (code "91") (name "Net-(I4-P)") (class "Default")
      (node (ref "I4") (pin "1") (pinfunction "P_1") (pintype "passive"))
      (node (ref "IC1") (pin "15") (pinfunction "A3_15") (pintype "input"))
      (node (ref "R7") (pin "2") (pinfunction "2_2") (pintype "passive"))
    )
    (net (code "92") (name "Net-(IC1A-Y4)") (class "Default")
      (node (ref "IC1") (pin "12") (pinfunction "Y4_12") (pintype "tri_state"))
      (node (ref "O1") (pin "1") (pinfunction "P_1") (pintype "passive"))
    )
    (net (code "93") (name "Net-(IC1B-Y1)") (class "Default")
      (node (ref "IC1") (pin "9") (pinfunction "Y1_9") (pintype "tri_state"))
      (node (ref "O2") (pin "1") (pinfunction "P_1") (pintype "passive"))
    )
    (net (code "94") (name "Net-(IC1B-Y2)") (class "Default")
      (node (ref "IC1") (pin "7") (pinfunction "Y2_7") (pintype "tri_state"))
      (node (ref "O3") (pin "1") (pinfunction "P_1") (pintype "passive"))
    )
    (net (code "95") (name "Net-(IC1B-Y3)") (class "Default")
      (node (ref "IC1") (pin "5") (pinfunction "Y3_5") (pintype "tri_state"))
      (node (ref "O4") (pin "1") (pinfunction "P_1") (pintype "passive"))
    )
    (net (code "96") (name "Net-(IC2-VBAT)") (class "Default")
      (node (ref "BAT") (pin "VCC") (pinfunction "VCC_VCC") (pintype "power_in"))
      (node (ref "IC2") (pin "3") (pinfunction "VBAT_3") (pintype "power_in"))
    )
    (net (code "97") (name "Net-(IC2-X1)") (class "Default")
      (node (ref "IC2") (pin "1") (pinfunction "X1_1") (pintype "bidirectional"))
      (node (ref "Q1") (pin "2") (pinfunction "2_2") (pintype "passive"))
    )
    (net (code "98") (name "Net-(IC2-X2)") (class "Default")
      (node (ref "IC2") (pin "2") (pinfunction "X2_2") (pintype "bidirectional"))
      (node (ref "Q1") (pin "1") (pinfunction "1_1") (pintype "passive"))
    )
    (net (code "99") (name "Net-(R1-Pad2)") (class "Default")
      (node (ref "R1") (pin "2") (pinfunction "2_2") (pintype "passive"))
      (node (ref "X5") (pin "8") (pinfunction "8_8") (pintype "bidirectional"))
    )
    (net (code "100") (name "Net-(R2-Pad2)") (class "Default")
      (node (ref "R2") (pin "2") (pinfunction "2_2") (pintype "passive"))
      (node (ref "X5") (pin "1") (pinfunction "1_1") (pintype "bidirectional"))
    )
    (net (code "101") (name "Net-(SCL.-P)") (class "Default")
      (node (ref "A16") (pin "SCL") (pinfunction "SCL/21_SCL") (pintype "bidirectional"))
      (node (ref "SCL.") (pin "1") (pinfunction "P_1") (pintype "passive"))
    )
    (net (code "102") (name "Net-(SDA.-P)") (class "Default")
      (node (ref "A16") (pin "SDA") (pinfunction "SDA/20_SDA") (pintype "bidirectional"))
      (node (ref "SDA.") (pin "1") (pinfunction "P_1") (pintype "passive"))
    )
    (net (code "103") (name "Net-(U1-VO)") (class "Default")
      (node (ref "3V3") (pin "1") (pinfunction "1_1") (pintype "passive"))
      (node (ref "C2") (pin "1") (pinfunction "1_1") (pintype "passive"))
      (node (ref "U1") (pin "1") (pinfunction "VO_1") (pintype "passive"))
    )
    (net (code "104") (name "Net-(VIN-P)") (class "Default")
      (node (ref "A16") (pin "VIN") (pinfunction "VIN_VIN") (pintype "power_in"))
      (node (ref "VIN") (pin "1") (pinfunction "P_1") (pintype "passive"))
    )
    (net (code "105") (name "Net-(X5-SW1)") (class "Default")
      (node (ref "SD_DETECT") (pin "1") (pinfunction "1_1") (pintype "passive"))
      (node (ref "X5") (pin "K1") (pinfunction "SW1_K1") (pintype "bidirectional"))
    )
    (net (code "106") (name "unconnected-(IC1B-Y4-Pad3)") (class "Default")
      (node (ref "IC1") (pin "3") (pinfunction "Y4_3") (pintype "tri_state"))
    )
  )
)
